# fireshield.net
KiCad netlist of a schematic drawn in EAGLE
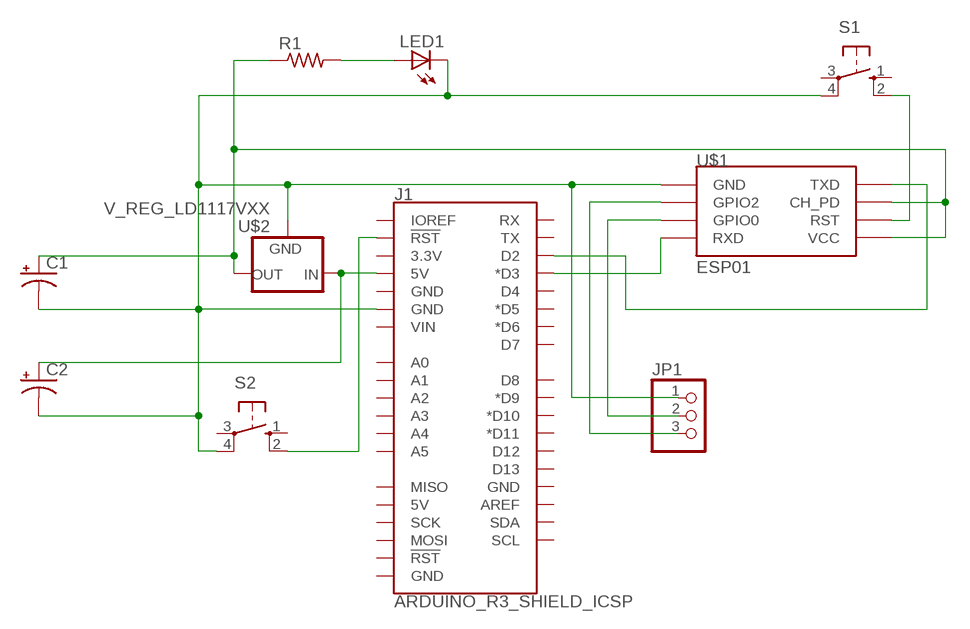
[diagram p0: schematic, sheet 1]

(export (version "E")
  (design (tool "Eeschema 10.0.6"))
  (components
    (comp (ref "C1")
      (value "10UF-25V-20%(PTH)KIT")
      (footprint "eagle-import:CPOL-RADIAL-10UF-25V-KIT")
      (libsource (lib "eagle-import") (part "10UF-25V-20%(PTH)KIT"))
    )
    (comp (ref "C2")
      (value "10UF-25V-20%(PTH)KIT")
      (footprint "eagle-import:CPOL-RADIAL-10UF-25V-KIT")
      (libsource (lib "eagle-import") (part "10UF-25V-20%(PTH)KIT"))
    )
    (comp (ref "J1")
      (value "ARDUINO_R3_SHIELD_ICSP")
      (footprint "eagle-import:UNO_R3_SHIELD_ICSP")
      (libsource (lib "eagle-import") (part "ARDUINO_R3_SHIELD_ICSP"))
    )
    (comp (ref "JP1")
      (value "PINHD-1X3")
      (footprint "eagle-import:1X03")
      (libsource (lib "eagle-import") (part "PINHD-1X3"))
    )
    (comp (ref "LED1")
      (value "LED3MM")
      (footprint "eagle-import:LED3MM")
      (libsource (lib "eagle-import") (part "LED3MM"))
    )
    (comp (ref "R1")
      (value "R-US_0207/10")
      (footprint "eagle-import:0207_10")
      (libsource (lib "eagle-import") (part "R-US_0207/10"))
    )
    (comp (ref "S1")
      (value "10-XX")
      (footprint "eagle-import:B3F-10XX")
      (fields (field (name "MPN") "B3F-1000"))
      (libsource (lib "eagle-import") (part "10-XX"))
    )
    (comp (ref "S2")
      (value "10-XX")
      (footprint "eagle-import:B3F-10XX")
      (fields (field (name "MPN") "B3F-1000"))
      (libsource (lib "eagle-import") (part "10-XX"))
    )
    (comp (ref "U$1")
      (value "ESP01")
      (footprint "eagle-import:ESP01")
      (libsource (lib "eagle-import") (part "ESP01"))
    )
    (comp (ref "U$2")
      (value "V_REG_LD1117VXX")
      (footprint "eagle-import:78XXL")
      (libsource (lib "eagle-import") (part "V_REG_LD1117VXX"))
    )
  )
  (nets
    (net (code "1") (name "Net-(C1-+)") (class "Default")
      (node (ref "C1") (pin "1") (pinfunction "+_1") (pintype "passive"))
      (node (ref "R1") (pin "1") (pinfunction "1_1") (pintype "passive"))
      (node (ref "U$1") (pin "CH_PD") (pinfunction "CH_PD_CH_PD") (pintype "bidirectional"))
      (node (ref "U$1") (pin "VCC") (pinfunction "VCC_VCC") (pintype "bidirectional"))
      (node (ref "U$2") (pin "GND") (pinfunction "OUT_GND") (pintype "passive"))
    )
    (net (code "2") (name "Net-(C1--)") (class "Default")
      (node (ref "C1") (pin "2") (pinfunction "-_2") (pintype "passive"))
      (node (ref "C2") (pin "2") (pinfunction "-_2") (pintype "passive"))
      (node (ref "J1") (pin "GND@1") (pinfunction "GND_GND@1") (pintype "bidirectional"))
      (node (ref "JP1") (pin "1") (pinfunction "1_1") (pintype "passive"))
      (node (ref "LED1") (pin "K") (pinfunction "C_K") (pintype "passive"))
      (node (ref "S1") (pin "4") (pinfunction "P1_4") (pintype "passive"))
      (node (ref "S2") (pin "4") (pinfunction "P1_4") (pintype "passive"))
      (node (ref "U$1") (pin "GND") (pinfunction "GND_GND") (pintype "bidirectional"))
      (node (ref "U$2") (pin "IN") (pinfunction "GND_IN") (pintype "input"))
    )
    (net (code "3") (name "Net-(C2-+)") (class "Default")
      (node (ref "C2") (pin "1") (pinfunction "+_1") (pintype "passive"))
      (node (ref "J1") (pin "5V") (pinfunction "5V_5V") (pintype "bidirectional"))
      (node (ref "U$2") (pin "OUT") (pinfunction "IN_OUT") (pintype "input"))
    )
    (net (code "4") (name "Net-(J1-*D3)") (class "Default")
      (node (ref "J1") (pin "D3") (pinfunction "*D3_D3") (pintype "bidirectional"))
      (node (ref "U$1") (pin "RX") (pinfunction "RXD_RX") (pintype "bidirectional"))
    )
    (net (code "5") (name "Net-(JP1-Pad2)") (class "Default")
      (node (ref "JP1") (pin "2") (pinfunction "2_2") (pintype "passive"))
      (node (ref "U$1") (pin "GPIO0") (pinfunction "GPIO0_GPIO0") (pintype "bidirectional"))
    )
    (net (code "6") (name "Net-(JP1-Pad3)") (class "Default")
      (node (ref "JP1") (pin "3") (pinfunction "3_3") (pintype "passive"))
      (node (ref "U$1") (pin "GPIO2") (pinfunction "GPIO2_GPIO2") (pintype "bidirectional"))
    )
    (net (code "7") (name "Net-(LED1-PadA)") (class "Default")
      (node (ref "LED1") (pin "A") (pinfunction "A_A") (pintype "passive"))
      (node (ref "R1") (pin "2") (pinfunction "2_2") (pintype "passive"))
    )
    (net (code "8") (name "Net-(S1-S1)") (class "Default")
      (node (ref "S1") (pin "2") (pinfunction "S1_2") (pintype "passive"))
      (node (ref "U$1") (pin "RST") (pinfunction "RST_RST") (pintype "bidirectional"))
    )
    (net (code "9") (name "Net-(S2-S1)") (class "Default")
      (node (ref "J1") (pin "RES") (pinfunction "~{RST}_RES") (pintype "bidirectional"))
      (node (ref "S2") (pin "2") (pinfunction "S1_2") (pintype "passive"))
    )
    (net (code "10") (name "Net-(U$1-TXD)") (class "Default")
      (node (ref "J1") (pin "D2") (pinfunction "D2_D2") (pintype "bidirectional"))
      (node (ref "U$1") (pin "TX") (pinfunction "TXD_TX") (pintype "bidirectional"))
    )
    (net (code "11") (name "unconnected-(J1-*D5-PadD5)") (class "Default")
      (node (ref "J1") (pin "D5") (pinfunction "*D5_D5") (pintype "bidirectional"))
    )
    (net (code "12") (name "unconnected-(J1-*D6-PadD6)") (class "Default")
      (node (ref "J1") (pin "D6") (pinfunction "*D6_D6") (pintype "bidirectional"))
    )
    (net (code "13") (name "unconnected-(J1-*D9-PadD9)") (class "Default")
      (node (ref "J1") (pin "D9") (pinfunction "*D9_D9") (pintype "bidirectional"))
    )
    (net (code "14") (name "unconnected-(J1-*D10-PadD10)") (class "Default")
      (node (ref "J1") (pin "D10") (pinfunction "*D10_D10") (pintype "bidirectional"))
    )
    (net (code "15") (name "unconnected-(J1-*D11-PadD11)") (class "Default")
      (node (ref "J1") (pin "D11") (pinfunction "*D11_D11") (pintype "bidirectional"))
    )
    (net (code "16") (name "unconnected-(J1-5V-Pad5V_ICSP)") (class "Default")
      (node (ref "J1") (pin "5V_ICSP") (pinfunction "5V_5V_ICSP") (pintype "bidirectional"))
    )
    (net (code "17") (name "unconnected-(J1-GND-PadGND@0)") (class "Default")
      (node (ref "J1") (pin "GND@0") (pinfunction "GND_GND@0") (pintype "bidirectional"))
    )
    (net (code "18") (name "unconnected-(J1-GND-PadGND@2)") (class "Default")
      (node (ref "J1") (pin "GND@2") (pinfunction "GND_GND@2") (pintype "bidirectional"))
    )
    (net (code "19") (name "unconnected-(J1-GND-PadGND_ICSP)") (class "Default")
      (node (ref "J1") (pin "GND_ICSP") (pinfunction "GND_GND_ICSP") (pintype "bidirectional"))
    )
    (net (code "20") (name "unconnected-(J1-Pad3.3V)") (class "Default")
      (node (ref "J1") (pin "3.3V") (pinfunction "3.3V_3.3V") (pintype "bidirectional"))
    )
    (net (code "21") (name "unconnected-(J1-PadA0)") (class "Default")
      (node (ref "J1") (pin "A0") (pinfunction "A0_A0") (pintype "bidirectional"))
    )
    (net (code "22") (name "unconnected-(J1-PadA1)") (class "Default")
      (node (ref "J1") (pin "A1") (pinfunction "A1_A1") (pintype "bidirectional"))
    )
    (net (code "23") (name "unconnected-(J1-PadA2)") (class "Default")
      (node (ref "J1") (pin "A2") (pinfunction "A2_A2") (pintype "bidirectional"))
    )
    (net (code "24") (name "unconnected-(J1-PadA3)") (class "Default")
      (node (ref "J1") (pin "A3") (pinfunction "A3_A3") (pintype "bidirectional"))
    )
    (net (code "25") (name "unconnected-(J1-PadA4)") (class "Default")
      (node (ref "J1") (pin "A4") (pinfunction "A4_A4") (pintype "bidirectional"))
    )
    (net (code "26") (name "unconnected-(J1-PadA5)") (class "Default")
      (node (ref "J1") (pin "A5") (pinfunction "A5_A5") (pintype "bidirectional"))
    )
    (net (code "27") (name "unconnected-(J1-PadAREF)") (class "Default")
      (node (ref "J1") (pin "AREF") (pinfunction "AREF_AREF") (pintype "bidirectional"))
    )
    (net (code "28") (name "unconnected-(J1-PadD4)") (class "Default")
      (node (ref "J1") (pin "D4") (pinfunction "D4_D4") (pintype "bidirectional"))
    )
    (net (code "29") (name "unconnected-(J1-PadD7)") (class "Default")
      (node (ref "J1") (pin "D7") (pinfunction "D7_D7") (pintype "bidirectional"))
    )
    (net (code "30") (name "unconnected-(J1-PadD8)") (class "Default")
      (node (ref "J1") (pin "D8") (pinfunction "D8_D8") (pintype "bidirectional"))
    )
    (net (code "31") (name "unconnected-(J1-PadD12)") (class "Default")
      (node (ref "J1") (pin "D12") (pinfunction "D12_D12") (pintype "bidirectional"))
    )
    (net (code "32") (name "unconnected-(J1-PadD13)") (class "Default")
      (node (ref "J1") (pin "D13") (pinfunction "D13_D13") (pintype "bidirectional"))
    )
    (net (code "33") (name "unconnected-(J1-PadIOREF)") (class "Default")
      (node (ref "J1") (pin "IOREF") (pinfunction "IOREF_IOREF") (pintype "bidirectional"))
    )
    (net (code "34") (name "unconnected-(J1-PadMISO)") (class "Default")
      (node (ref "J1") (pin "MISO") (pinfunction "MISO_MISO") (pintype "bidirectional"))
    )
    (net (code "35") (name "unconnected-(J1-PadMOSI)") (class "Default")
      (node (ref "J1") (pin "MOSI") (pinfunction "MOSI_MOSI") (pintype "bidirectional"))
    )
    (net (code "36") (name "unconnected-(J1-PadRX)") (class "Default")
      (node (ref "J1") (pin "RX") (pinfunction "RX_RX") (pintype "bidirectional"))
    )
    (net (code "37") (name "unconnected-(J1-PadSCK)") (class "Default")
      (node (ref "J1") (pin "SCK") (pinfunction "SCK_SCK") (pintype "bidirectional"))
    )
    (net (code "38") (name "unconnected-(J1-PadSCL)") (class "Default")
      (node (ref "J1") (pin "SCL") (pinfunction "SCL_SCL") (pintype "bidirectional"))
    )
    (net (code "39") (name "unconnected-(J1-PadSDA)") (class "Default")
      (node (ref "J1") (pin "SDA") (pinfunction "SDA_SDA") (pintype "bidirectional"))
    )
    (net (code "40") (name "unconnected-(J1-PadTX)") (class "Default")
      (node (ref "J1") (pin "TX") (pinfunction "TX_TX") (pintype "bidirectional"))
    )
    (net (code "41") (name "unconnected-(J1-PadVIN)") (class "Default")
      (node (ref "J1") (pin "VIN") (pinfunction "VIN_VIN") (pintype "bidirectional"))
    )
    (net (code "42") (name "unconnected-(J1-~{RST}-PadRST_ICSP)") (class "Default")
      (node (ref "J1") (pin "RST_ICSP") (pinfunction "~{RST}_RST_ICSP") (pintype "bidirectional"))
    )
    (net (code "43") (name "unconnected-(S1-P-Pad3)") (class "Default")
      (node (ref "S1") (pin "3") (pinfunction "P_3") (pintype "passive"))
    )
    (net (code "44") (name "unconnected-(S1-S-Pad1)") (class "Default")
      (node (ref "S1") (pin "1") (pinfunction "S_1") (pintype "passive"))
    )
    (net (code "45") (name "unconnected-(S2-P-Pad3)") (class "Default")
      (node (ref "S2") (pin "3") (pinfunction "P_3") (pintype "passive"))
    )
    (net (code "46") (name "unconnected-(S2-S-Pad1)") (class "Default")
      (node (ref "S2") (pin "1") (pinfunction "S_1") (pintype "passive"))
    )
  )
)
